# ENC28j60BO.net
KiCad netlist of a schematic drawn in EAGLE
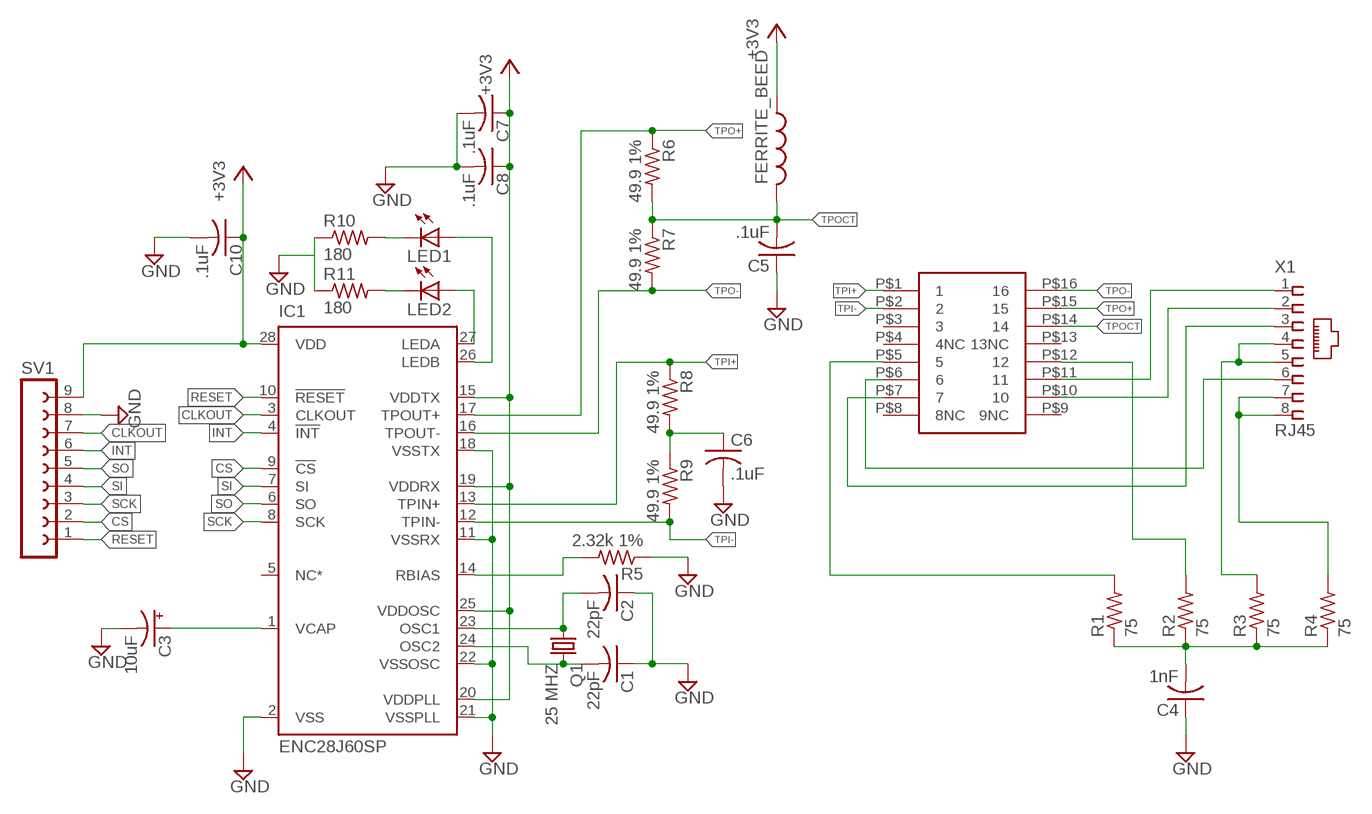
[diagram p0: schematic, sheet 1]

(export (version "E")
  (design (tool "Eeschema 10.0.6"))
  (components
    (comp (ref "C1")
      (value "22pF")
      (footprint "eagle-import:C025-024X044")
      (libsource (lib "eagle-import") (part "C-US025-024X044"))
    )
    (comp (ref "C2")
      (value "22pF")
      (footprint "eagle-import:C025-024X044")
      (libsource (lib "eagle-import") (part "C-US025-024X044"))
    )
    (comp (ref "C3")
      (value "10uF")
      (footprint "eagle-import:E2,5-6E")
      (libsource (lib "eagle-import") (part "CPOL-USE2,5-6E"))
    )
    (comp (ref "C4")
      (value "1nF")
      (footprint "eagle-import:C050-025X075")
      (libsource (lib "eagle-import") (part "C-US050-025X075"))
    )
    (comp (ref "C5")
      (value ".1uF")
      (footprint "eagle-import:C050-024X044")
      (libsource (lib "eagle-import") (part "C-US050-024X044"))
    )
    (comp (ref "C6")
      (value ".1uF")
      (footprint "eagle-import:C050-024X044")
      (libsource (lib "eagle-import") (part "C-US050-024X044"))
    )
    (comp (ref "C7")
      (value ".1uF")
      (footprint "eagle-import:C050-024X044")
      (libsource (lib "eagle-import") (part "C-US050-024X044"))
    )
    (comp (ref "C8")
      (value ".1uF")
      (footprint "eagle-import:C050-024X044")
      (libsource (lib "eagle-import") (part "C-US050-024X044"))
    )
    (comp (ref "C10")
      (value ".1uF")
      (footprint "eagle-import:C050-024X044")
      (libsource (lib "eagle-import") (part "C-US050-024X044"))
    )
    (comp (ref "FERRITE_BEED")
      (value "L-US0204/7")
      (footprint "eagle-import:0204_7")
      (libsource (lib "eagle-import") (part "L-US0204/7"))
    )
    (comp (ref "IC1")
      (value "ENC28J60SP")
      (footprint "eagle-import:DIL28-3")
      (fields (field (name "MF") "MICROCHIP") (field (name "MPN") "ENC28J60/SP"))
      (libsource (lib "eagle-import") (part "ENC28J60SP"))
    )
    (comp (ref "LED1")
      (value "LED3MM")
      (footprint "eagle-import:LED3MM")
      (libsource (lib "eagle-import") (part "LED3MM"))
    )
    (comp (ref "LED2")
      (value "LED3MM")
      (footprint "eagle-import:LED3MM")
      (libsource (lib "eagle-import") (part "LED3MM"))
    )
    (comp (ref "Q1")
      (value "25 MHZ")
      (footprint "eagle-import:HC49U-V")
      (libsource (lib "eagle-import") (part "CRYSTALHC49U-V"))
    )
    (comp (ref "R1")
      (value "75")
      (footprint "eagle-import:0204_7")
      (libsource (lib "eagle-import") (part "R-US_0204/7"))
    )
    (comp (ref "R2")
      (value "75")
      (footprint "eagle-import:0204_7")
      (libsource (lib "eagle-import") (part "R-US_0204/7"))
    )
    (comp (ref "R3")
      (value "75")
      (footprint "eagle-import:0204_7")
      (libsource (lib "eagle-import") (part "R-US_0204/7"))
    )
    (comp (ref "R4")
      (value "75")
      (footprint "eagle-import:0204_7")
      (libsource (lib "eagle-import") (part "R-US_0204/7"))
    )
    (comp (ref "R5")
      (value "2.32k 1%")
      (footprint "eagle-import:0204_7")
      (libsource (lib "eagle-import") (part "R-US_0204/7"))
    )
    (comp (ref "R6")
      (value "49.9 1%")
      (footprint "eagle-import:0204_7")
      (libsource (lib "eagle-import") (part "R-US_0204/7"))
    )
    (comp (ref "R7")
      (value "49.9 1%")
      (footprint "eagle-import:0204_7")
      (libsource (lib "eagle-import") (part "R-US_0204/7"))
    )
    (comp (ref "R8")
      (value "49.9 1%")
      (footprint "eagle-import:0204_7")
      (libsource (lib "eagle-import") (part "R-US_0204/7"))
    )
    (comp (ref "R9")
      (value "49.9 1%")
      (footprint "eagle-import:0204_7")
      (libsource (lib "eagle-import") (part "R-US_0204/7"))
    )
    (comp (ref "R10")
      (value "180")
      (footprint "eagle-import:0204_7")
      (libsource (lib "eagle-import") (part "R-US_0204/7"))
    )
    (comp (ref "R11")
      (value "180")
      (footprint "eagle-import:0204_7")
      (libsource (lib "eagle-import") (part "R-US_0204/7"))
    )
    (comp (ref "SV1")
      (value "FE09-1")
      (footprint "eagle-import:FE09")
      (libsource (lib "eagle-import") (part "FE09-1"))
    )
    (comp (ref "U$1")
      (value "S558-5999-46-F")
      (footprint "eagle-import:DIP16SMD")
      (libsource (lib "eagle-import") (part "S558-5999-46-F"))
    )
    (comp (ref "X1")
      (value "RJ45")
      (footprint "eagle-import:RJ45")
      (libsource (lib "eagle-import") (part "RJ45"))
    )
  )
  (nets
    (net (code "1") (name "+3V3") (class "Default")
      (node (ref "C10") (pin "1") (pinfunction "1_1") (pintype "passive"))
      (node (ref "C7") (pin "1") (pinfunction "1_1") (pintype "passive"))
      (node (ref "C8") (pin "1") (pinfunction "1_1") (pintype "passive"))
      (node (ref "FERRITE_BEED") (pin "1") (pinfunction "1_1") (pintype "passive"))
      (node (ref "IC1") (pin "15") (pinfunction "VDDTX_15") (pintype "input"))
      (node (ref "IC1") (pin "19") (pinfunction "VDDRX_19") (pintype "input"))
      (node (ref "IC1") (pin "20") (pinfunction "VDDPLL_20") (pintype "input"))
      (node (ref "IC1") (pin "25") (pinfunction "VDDOSC_25") (pintype "input"))
      (node (ref "IC1") (pin "28") (pinfunction "VDD_28") (pintype "input"))
      (node (ref "SV1") (pin "9") (pinfunction "9_9") (pintype "passive"))
    )
    (net (code "2") (name "CLKOUT") (class "Default")
      (node (ref "IC1") (pin "3") (pinfunction "CLKOUT_3") (pintype "output"))
      (node (ref "SV1") (pin "7") (pinfunction "7_7") (pintype "passive"))
    )
    (net (code "3") (name "CS") (class "Default")
      (node (ref "IC1") (pin "9") (pinfunction "~{CS}_9") (pintype "input"))
      (node (ref "SV1") (pin "2") (pinfunction "2_2") (pintype "passive"))
    )
    (net (code "4") (name "GND") (class "Default")
      (node (ref "C1") (pin "1") (pinfunction "1_1") (pintype "passive"))
      (node (ref "C10") (pin "2") (pinfunction "2_2") (pintype "passive"))
      (node (ref "C2") (pin "1") (pinfunction "1_1") (pintype "passive"))
      (node (ref "C3") (pin "-") (pinfunction "-_-") (pintype "passive"))
      (node (ref "C4") (pin "1") (pinfunction "1_1") (pintype "passive"))
      (node (ref "C5") (pin "1") (pinfunction "1_1") (pintype "passive"))
      (node (ref "C6") (pin "2") (pinfunction "2_2") (pintype "passive"))
      (node (ref "C7") (pin "2") (pinfunction "2_2") (pintype "passive"))
      (node (ref "C8") (pin "2") (pinfunction "2_2") (pintype "passive"))
      (node (ref "IC1") (pin "11") (pinfunction "VSSRX_11") (pintype "input"))
      (node (ref "IC1") (pin "18") (pinfunction "VSSTX_18") (pintype "input"))
      (node (ref "IC1") (pin "2") (pinfunction "VSS_2") (pintype "input"))
      (node (ref "IC1") (pin "21") (pinfunction "VSSPLL_21") (pintype "input"))
      (node (ref "IC1") (pin "22") (pinfunction "VSSOSC_22") (pintype "input"))
      (node (ref "R10") (pin "1") (pinfunction "1_1") (pintype "passive"))
      (node (ref "R11") (pin "1") (pinfunction "1_1") (pintype "passive"))
      (node (ref "R5") (pin "1") (pinfunction "1_1") (pintype "passive"))
      (node (ref "SV1") (pin "8") (pinfunction "8_8") (pintype "passive"))
    )
    (net (code "5") (name "INT") (class "Default")
      (node (ref "IC1") (pin "4") (pinfunction "~{INT}_4") (pintype "output"))
      (node (ref "SV1") (pin "6") (pinfunction "6_6") (pintype "passive"))
    )
    (net (code "6") (name "Net-(C4-Pad2)") (class "Default")
      (node (ref "C4") (pin "2") (pinfunction "2_2") (pintype "passive"))
      (node (ref "R1") (pin "1") (pinfunction "1_1") (pintype "passive"))
      (node (ref "R2") (pin "1") (pinfunction "1_1") (pintype "passive"))
      (node (ref "R3") (pin "1") (pinfunction "1_1") (pintype "passive"))
      (node (ref "R4") (pin "1") (pinfunction "1_1") (pintype "passive"))
    )
    (net (code "7") (name "Net-(C6-Pad1)") (class "Default")
      (node (ref "C6") (pin "1") (pinfunction "1_1") (pintype "passive"))
      (node (ref "R8") (pin "2") (pinfunction "2_2") (pintype "passive"))
      (node (ref "R9") (pin "1") (pinfunction "1_1") (pintype "passive"))
    )
    (net (code "8") (name "Net-(IC1-LEDA)") (class "Default")
      (node (ref "IC1") (pin "27") (pinfunction "LEDA_27") (pintype "output"))
      (node (ref "LED2") (pin "A") (pinfunction "A_A") (pintype "passive"))
    )
    (net (code "9") (name "Net-(IC1-LEDB)") (class "Default")
      (node (ref "IC1") (pin "26") (pinfunction "LEDB_26") (pintype "output"))
      (node (ref "LED1") (pin "A") (pinfunction "A_A") (pintype "passive"))
    )
    (net (code "10") (name "Net-(IC1-OSC1)") (class "Default")
      (node (ref "C2") (pin "2") (pinfunction "2_2") (pintype "passive"))
      (node (ref "IC1") (pin "23") (pinfunction "OSC1_23") (pintype "input"))
      (node (ref "Q1") (pin "1") (pinfunction "1_1") (pintype "passive"))
    )
    (net (code "11") (name "Net-(IC1-OSC2)") (class "Default")
      (node (ref "C1") (pin "2") (pinfunction "2_2") (pintype "passive"))
      (node (ref "IC1") (pin "24") (pinfunction "OSC2_24") (pintype "output"))
      (node (ref "Q1") (pin "2") (pinfunction "2_2") (pintype "passive"))
    )
    (net (code "12") (name "Net-(IC1-RBIAS)") (class "Default")
      (node (ref "IC1") (pin "14") (pinfunction "RBIAS_14") (pintype "input"))
      (node (ref "R5") (pin "2") (pinfunction "2_2") (pintype "passive"))
    )
    (net (code "13") (name "Net-(IC1-VCAP)") (class "Default")
      (node (ref "C3") (pin "+") (pinfunction "+_+") (pintype "passive"))
      (node (ref "IC1") (pin "1") (pinfunction "VCAP_1") (pintype "input"))
    )
    (net (code "14") (name "Net-(LED1-C)") (class "Default")
      (node (ref "LED1") (pin "K") (pinfunction "C_K") (pintype "passive"))
      (node (ref "R10") (pin "2") (pinfunction "2_2") (pintype "passive"))
    )
    (net (code "15") (name "Net-(LED2-C)") (class "Default")
      (node (ref "LED2") (pin "K") (pinfunction "C_K") (pintype "passive"))
      (node (ref "R11") (pin "2") (pinfunction "2_2") (pintype "passive"))
    )
    (net (code "16") (name "Net-(R3-Pad2)") (class "Default")
      (node (ref "R3") (pin "2") (pinfunction "2_2") (pintype "passive"))
      (node (ref "X1") (pin "4") (pinfunction "4_4") (pintype "passive"))
      (node (ref "X1") (pin "5") (pinfunction "5_5") (pintype "passive"))
    )
    (net (code "17") (name "Net-(R4-Pad2)") (class "Default")
      (node (ref "R4") (pin "2") (pinfunction "2_2") (pintype "passive"))
      (node (ref "X1") (pin "7") (pinfunction "7_7") (pintype "passive"))
      (node (ref "X1") (pin "8") (pinfunction "8_8") (pintype "passive"))
    )
    (net (code "18") (name "Net-(U$1-5)") (class "Default")
      (node (ref "R1") (pin "2") (pinfunction "2_2") (pintype "passive"))
      (node (ref "U$1") (pin "P$5") (pinfunction "5_P$5") (pintype "bidirectional"))
    )
    (net (code "19") (name "Net-(U$1-6)") (class "Default")
      (node (ref "U$1") (pin "P$6") (pinfunction "6_P$6") (pintype "bidirectional"))
      (node (ref "X1") (pin "6") (pinfunction "6_6") (pintype "passive"))
    )
    (net (code "20") (name "Net-(U$1-7)") (class "Default")
      (node (ref "U$1") (pin "P$7") (pinfunction "7_P$7") (pintype "bidirectional"))
      (node (ref "X1") (pin "3") (pinfunction "3_3") (pintype "passive"))
    )
    (net (code "21") (name "Net-(U$1-10)") (class "Default")
      (node (ref "U$1") (pin "P$10") (pinfunction "10_P$10") (pintype "bidirectional"))
      (node (ref "X1") (pin "2") (pinfunction "2_2") (pintype "passive"))
    )
    (net (code "22") (name "Net-(U$1-11)") (class "Default")
      (node (ref "U$1") (pin "P$11") (pinfunction "11_P$11") (pintype "bidirectional"))
      (node (ref "X1") (pin "1") (pinfunction "1_1") (pintype "passive"))
    )
    (net (code "23") (name "Net-(U$1-12)") (class "Default")
      (node (ref "R2") (pin "2") (pinfunction "2_2") (pintype "passive"))
      (node (ref "U$1") (pin "P$12") (pinfunction "12_P$12") (pintype "bidirectional"))
    )
    (net (code "24") (name "RESET") (class "Default")
      (node (ref "IC1") (pin "10") (pinfunction "~{RESET}_10") (pintype "input"))
      (node (ref "SV1") (pin "1") (pinfunction "1_1") (pintype "passive"))
    )
    (net (code "25") (name "SCK") (class "Default")
      (node (ref "IC1") (pin "8") (pinfunction "SCK_8") (pintype "input"))
      (node (ref "SV1") (pin "3") (pinfunction "3_3") (pintype "passive"))
    )
    (net (code "26") (name "SI") (class "Default")
      (node (ref "IC1") (pin "7") (pinfunction "SI_7") (pintype "input"))
      (node (ref "SV1") (pin "4") (pinfunction "4_4") (pintype "passive"))
    )
    (net (code "27") (name "SO") (class "Default")
      (node (ref "IC1") (pin "6") (pinfunction "SO_6") (pintype "output"))
      (node (ref "SV1") (pin "5") (pinfunction "5_5") (pintype "passive"))
    )
    (net (code "28") (name "TPI+") (class "Default")
      (node (ref "IC1") (pin "13") (pinfunction "TPIN+_13") (pintype "input"))
      (node (ref "R8") (pin "1") (pinfunction "1_1") (pintype "passive"))
      (node (ref "U$1") (pin "P$1") (pinfunction "1_P$1") (pintype "bidirectional"))
    )
    (net (code "29") (name "TPI-") (class "Default")
      (node (ref "IC1") (pin "12") (pinfunction "TPIN-_12") (pintype "input"))
      (node (ref "R9") (pin "2") (pinfunction "2_2") (pintype "passive"))
      (node (ref "U$1") (pin "P$2") (pinfunction "2_P$2") (pintype "bidirectional"))
    )
    (net (code "30") (name "TPO+") (class "Default")
      (node (ref "IC1") (pin "17") (pinfunction "TPOUT+_17") (pintype "output"))
      (node (ref "R6") (pin "1") (pinfunction "1_1") (pintype "passive"))
      (node (ref "U$1") (pin "P$15") (pinfunction "15_P$15") (pintype "bidirectional"))
    )
    (net (code "31") (name "TPO-") (class "Default")
      (node (ref "IC1") (pin "16") (pinfunction "TPOUT-_16") (pintype "output"))
      (node (ref "R7") (pin "2") (pinfunction "2_2") (pintype "passive"))
      (node (ref "U$1") (pin "P$16") (pinfunction "16_P$16") (pintype "bidirectional"))
    )
    (net (code "32") (name "TPOCT") (class "Default")
      (node (ref "C5") (pin "2") (pinfunction "2_2") (pintype "passive"))
      (node (ref "FERRITE_BEED") (pin "2") (pinfunction "2_2") (pintype "passive"))
      (node (ref "R6") (pin "2") (pinfunction "2_2") (pintype "passive"))
      (node (ref "R7") (pin "1") (pinfunction "1_1") (pintype "passive"))
      (node (ref "U$1") (pin "P$14") (pinfunction "14_P$14") (pintype "bidirectional"))
    )
    (net (code "33") (name "unconnected-(IC1-NC*-Pad5)") (class "Default")
      (node (ref "IC1") (pin "5") (pinfunction "NC*_5") (pintype "output"))
    )
    (net (code "34") (name "unconnected-(U$1-3-PadP$3)") (class "Default")
      (node (ref "U$1") (pin "P$3") (pinfunction "3_P$3") (pintype "bidirectional"))
    )
    (net (code "35") (name "unconnected-(U$1-4NC-PadP$4)") (class "Default")
      (node (ref "U$1") (pin "P$4") (pinfunction "4NC_P$4") (pintype "bidirectional"))
    )
    (net (code "36") (name "unconnected-(U$1-8NC-PadP$8)") (class "Default")
      (node (ref "U$1") (pin "P$8") (pinfunction "8NC_P$8") (pintype "bidirectional"))
    )
    (net (code "37") (name "unconnected-(U$1-9NC-PadP$9)") (class "Default")
      (node (ref "U$1") (pin "P$9") (pinfunction "9NC_P$9") (pintype "bidirectional"))
    )
    (net (code "38") (name "unconnected-(U$1-13NC-PadP$13)") (class "Default")
      (node (ref "U$1") (pin "P$13") (pinfunction "13NC_P$13") (pintype "bidirectional"))
    )
  )
)
